# board_power.net
KiCad netlist of a schematic drawn in EAGLE
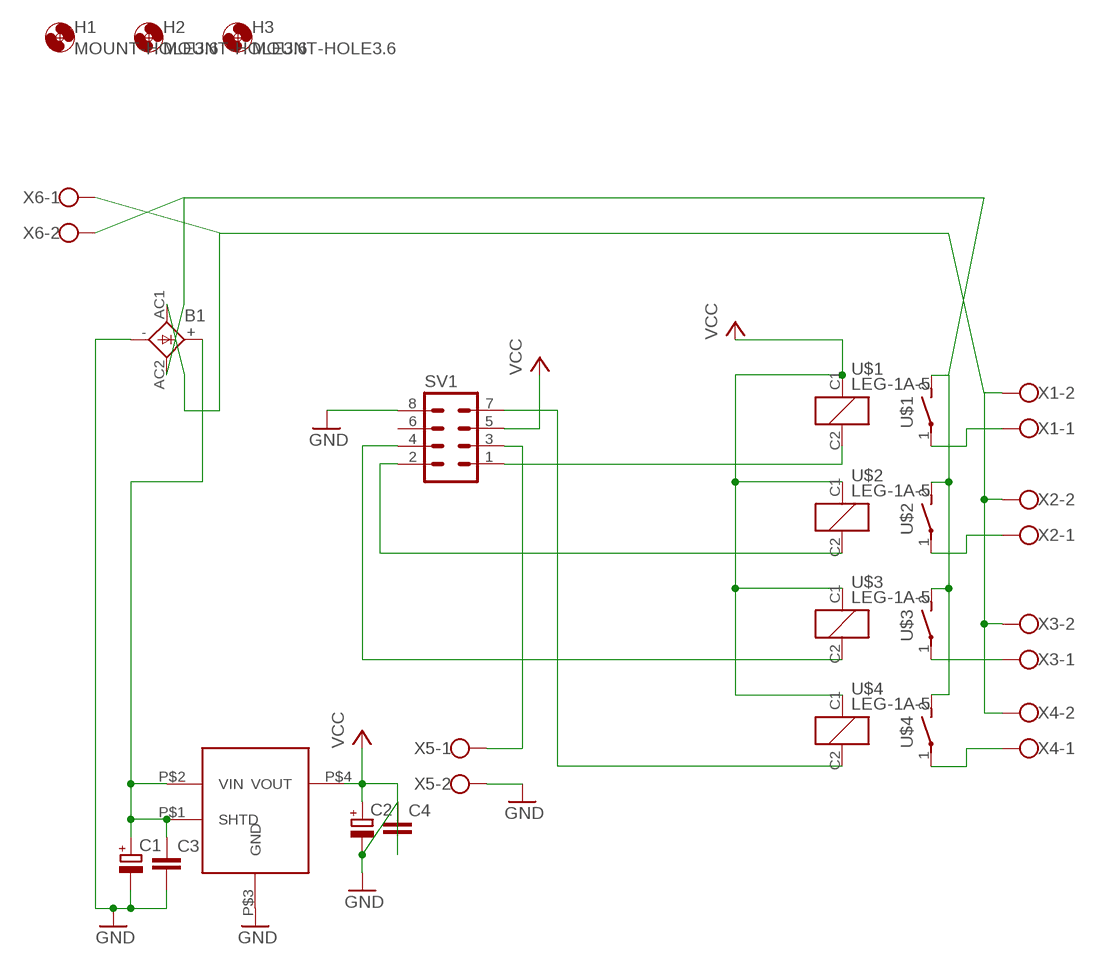
[diagram p0: schematic, sheet 1]

(export (version "E")
  (design (tool "Eeschema 10.0.6"))
  (components
    (comp (ref "B1")
      (value "KBK10A")
      (footprint "eagle-import:KBK10A")
      (libsource (lib "eagle-import") (part "KBK10A"))
    )
    (comp (ref "C1")
      (value "CPOL-EUE5-4")
      (footprint "eagle-import:E5-4")
      (libsource (lib "eagle-import") (part "CPOL-EUE5-4"))
    )
    (comp (ref "C2")
      (value "CPOL-EUE5-4")
      (footprint "eagle-import:E5-4")
      (libsource (lib "eagle-import") (part "CPOL-EUE5-4"))
    )
    (comp (ref "C3")
      (value "C-EU025_050-025X075")
      (footprint "eagle-import:C025_050-025X075")
      (libsource (lib "eagle-import") (part "C-EU025_050-025X075"))
    )
    (comp (ref "C4")
      (value "C-EU025_050-025X075")
      (footprint "eagle-import:C025_050-025X075")
      (libsource (lib "eagle-import") (part "C-EU025_050-025X075"))
    )
    (comp (ref "H1")
      (value "MOUNT-HOLE3.6")
      (footprint "eagle-import:3,6")
      (libsource (lib "eagle-import") (part "MOUNT-HOLE3.6"))
    )
    (comp (ref "H2")
      (value "MOUNT-HOLE3.6")
      (footprint "eagle-import:3,6")
      (libsource (lib "eagle-import") (part "MOUNT-HOLE3.6"))
    )
    (comp (ref "H3")
      (value "MOUNT-HOLE3.6")
      (footprint "eagle-import:3,6")
      (libsource (lib "eagle-import") (part "MOUNT-HOLE3.6"))
    )
    (comp (ref "SV1")
      (value "MA04-2")
      (footprint "eagle-import:MA04-2")
      (libsource (lib "eagle-import") (part "MA04-2"))
    )
    (comp (ref "U$1")
      (value "LEG-1A-5")
      (footprint "eagle-import:LEG")
      (libsource (lib "eagle-import") (part "LEG-1A-5"))
    )
    (comp (ref "U$2")
      (value "LEG-1A-5")
      (footprint "eagle-import:LEG")
      (libsource (lib "eagle-import") (part "LEG-1A-5"))
    )
    (comp (ref "U$3")
      (value "LEG-1A-5")
      (footprint "eagle-import:LEG")
      (libsource (lib "eagle-import") (part "LEG-1A-5"))
    )
    (comp (ref "U$4")
      (value "LEG-1A-5")
      (footprint "eagle-import:LEG")
      (libsource (lib "eagle-import") (part "LEG-1A-5"))
    )
    (comp (ref "U$5")
      (value "POLOLU-2098")
      (footprint "eagle-import:POLOLU-2098")
      (libsource (lib "eagle-import") (part "POLOLU-2098"))
    )
    (comp (ref "X1")
      (value "PASSO3")
      (footprint "eagle-import:PASSO3")
      (fields (field (name "MPN") "237-102"))
      (libsource (lib "eagle-import") (part "PASSO3"))
    )
    (comp (ref "X2")
      (value "PASSO3")
      (footprint "eagle-import:PASSO3")
      (fields (field (name "MPN") "237-102"))
      (libsource (lib "eagle-import") (part "PASSO3"))
    )
    (comp (ref "X3")
      (value "PASSO3")
      (footprint "eagle-import:PASSO3")
      (fields (field (name "MPN") "237-102"))
      (libsource (lib "eagle-import") (part "PASSO3"))
    )
    (comp (ref "X4")
      (value "PASSO3")
      (footprint "eagle-import:PASSO3")
      (fields (field (name "MPN") "237-102"))
      (libsource (lib "eagle-import") (part "PASSO3"))
    )
    (comp (ref "X5")
      (value "PASSO3")
      (footprint "eagle-import:PASSO3")
      (fields (field (name "MPN") "237-102"))
      (libsource (lib "eagle-import") (part "PASSO3"))
    )
    (comp (ref "X6")
      (value "PASSO3")
      (footprint "eagle-import:PASSO3")
      (fields (field (name "MPN") "237-102"))
      (libsource (lib "eagle-import") (part "PASSO3"))
    )
  )
  (nets
    (net (code "1") (name "GND") (class "Default")
      (node (ref "B1") (pin "-") (pinfunction "-_-") (pintype "passive"))
      (node (ref "C1") (pin "-") (pinfunction "-_-") (pintype "passive"))
      (node (ref "C2") (pin "-") (pinfunction "-_-") (pintype "passive"))
      (node (ref "C3") (pin "2") (pinfunction "2_2") (pintype "passive"))
      (node (ref "C4") (pin "1") (pinfunction "1_1") (pintype "passive"))
      (node (ref "SV1") (pin "8") (pinfunction "8_8") (pintype "passive"))
      (node (ref "U$5") (pin "P$3") (pinfunction "GND_P$3") (pintype "bidirectional"))
      (node (ref "X5") (pin "2") (pinfunction "KL_2") (pintype "passive"))
    )
    (net (code "2") (name "Net-(U$1A-P)") (class "Default")
      (node (ref "U$1") (pin "1") (pinfunction "P_1") (pintype "passive"))
      (node (ref "X1") (pin "1") (pinfunction "KL_1") (pintype "passive"))
    )
    (net (code "3") (name "Net-(U$1A-S)") (class "Default")
      (node (ref "B1") (pin "AC2") (pinfunction "AC2_AC2") (pintype "passive"))
      (node (ref "U$1") (pin "2") (pinfunction "S_2") (pintype "passive"))
      (node (ref "U$2") (pin "2") (pinfunction "S_2") (pintype "passive"))
      (node (ref "U$3") (pin "2") (pinfunction "S_2") (pintype "passive"))
      (node (ref "U$4") (pin "2") (pinfunction "S_2") (pintype "passive"))
      (node (ref "X6") (pin "2") (pinfunction "KL_2") (pintype "passive"))
    )
    (net (code "4") (name "Net-(U$1B-2)") (class "Default")
      (node (ref "SV1") (pin "1") (pinfunction "1_1") (pintype "passive"))
      (node (ref "U$1") (pin "C2") (pinfunction "2_C2") (pintype "passive"))
    )
    (net (code "5") (name "Net-(U$2A-P)") (class "Default")
      (node (ref "U$2") (pin "1") (pinfunction "P_1") (pintype "passive"))
      (node (ref "X2") (pin "1") (pinfunction "KL_1") (pintype "passive"))
    )
    (net (code "6") (name "Net-(U$2B-2)") (class "Default")
      (node (ref "SV1") (pin "2") (pinfunction "2_2") (pintype "passive"))
      (node (ref "U$2") (pin "C2") (pinfunction "2_C2") (pintype "passive"))
    )
    (net (code "7") (name "Net-(U$3A-P)") (class "Default")
      (node (ref "U$3") (pin "1") (pinfunction "P_1") (pintype "passive"))
      (node (ref "X3") (pin "1") (pinfunction "KL_1") (pintype "passive"))
    )
    (net (code "8") (name "Net-(U$3B-2)") (class "Default")
      (node (ref "SV1") (pin "4") (pinfunction "4_4") (pintype "passive"))
      (node (ref "U$3") (pin "C2") (pinfunction "2_C2") (pintype "passive"))
    )
    (net (code "9") (name "Net-(U$4A-P)") (class "Default")
      (node (ref "U$4") (pin "1") (pinfunction "P_1") (pintype "passive"))
      (node (ref "X4") (pin "1") (pinfunction "KL_1") (pintype "passive"))
    )
    (net (code "10") (name "Net-(U$4B-2)") (class "Default")
      (node (ref "SV1") (pin "7") (pinfunction "7_7") (pintype "passive"))
      (node (ref "U$4") (pin "C2") (pinfunction "2_C2") (pintype "passive"))
    )
    (net (code "11") (name "Net-(U$5-SHTD)") (class "Default")
      (node (ref "B1") (pin "+") (pinfunction "+_+") (pintype "passive"))
      (node (ref "C1") (pin "+") (pinfunction "+_+") (pintype "passive"))
      (node (ref "C3") (pin "1") (pinfunction "1_1") (pintype "passive"))
      (node (ref "U$5") (pin "P$1") (pinfunction "SHTD_P$1") (pintype "power_in"))
      (node (ref "U$5") (pin "P$2") (pinfunction "VIN_P$2") (pintype "power_in"))
    )
    (net (code "12") (name "Net-(X1B-KL)") (class "Default")
      (node (ref "B1") (pin "AC1") (pinfunction "AC1_AC1") (pintype "passive"))
      (node (ref "X1") (pin "2") (pinfunction "KL_2") (pintype "passive"))
      (node (ref "X2") (pin "2") (pinfunction "KL_2") (pintype "passive"))
      (node (ref "X3") (pin "2") (pinfunction "KL_2") (pintype "passive"))
      (node (ref "X4") (pin "2") (pinfunction "KL_2") (pintype "passive"))
      (node (ref "X6") (pin "1") (pinfunction "KL_1") (pintype "passive"))
    )
    (net (code "13") (name "Net-(X5A-KL)") (class "Default")
      (node (ref "SV1") (pin "3") (pinfunction "3_3") (pintype "passive"))
      (node (ref "X5") (pin "1") (pinfunction "KL_1") (pintype "passive"))
    )
    (net (code "14") (name "VCC") (class "Default")
      (node (ref "C2") (pin "+") (pinfunction "+_+") (pintype "passive"))
      (node (ref "C4") (pin "2") (pinfunction "2_2") (pintype "passive"))
      (node (ref "SV1") (pin "5") (pinfunction "5_5") (pintype "passive"))
      (node (ref "U$1") (pin "C1") (pinfunction "1_C1") (pintype "passive"))
      (node (ref "U$2") (pin "C1") (pinfunction "1_C1") (pintype "passive"))
      (node (ref "U$3") (pin "C1") (pinfunction "1_C1") (pintype "passive"))
      (node (ref "U$4") (pin "C1") (pinfunction "1_C1") (pintype "passive"))
      (node (ref "U$5") (pin "P$4") (pinfunction "VOUT_P$4") (pintype "bidirectional"))
    )
    (net (code "15") (name "unconnected-(SV1-Pad6)") (class "Default")
      (node (ref "SV1") (pin "6") (pinfunction "6_6") (pintype "passive"))
    )
  )
)
